# AtmelSMD328NRF.net
KiCad netlist of a schematic drawn in EAGLE
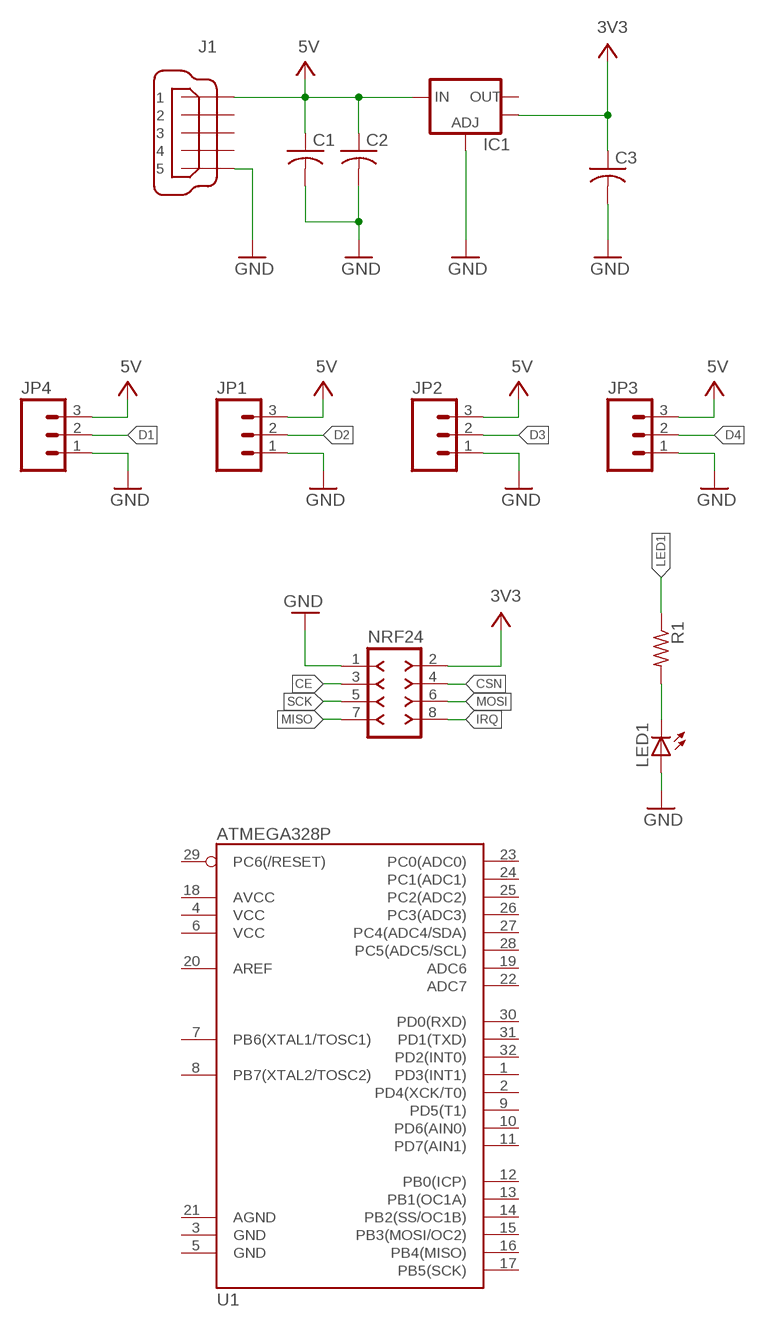
[diagram p0: schematic, sheet 1]

(export (version "E")
  (design (tool "Eeschema 10.0.6"))
  (components
    (comp (ref "C1")
      (value "C-USC0805")
      (footprint "eagle-import:C0805")
      (libsource (lib "eagle-import") (part "C-USC0805"))
    )
    (comp (ref "C2")
      (value "C-USC0805")
      (footprint "eagle-import:C0805")
      (libsource (lib "eagle-import") (part "C-USC0805"))
    )
    (comp (ref "C3")
      (value "C-USC0805")
      (footprint "eagle-import:C0805")
      (libsource (lib "eagle-import") (part "C-USC0805"))
    )
    (comp (ref "IC1")
      (value "V_REG_LM1117SOT223")
      (footprint "eagle-import:SOT223")
      (libsource (lib "eagle-import") (part "V_REG_LM1117SOT223"))
    )
    (comp (ref "J1")
      (value "MICRO-USB-ZX62R-B-5P")
      (footprint "eagle-import:ZX62R-B-5P")
      (libsource (lib "eagle-import") (part "MICRO-USB-ZX62R-B-5P"))
    )
    (comp (ref "JP1")
      (value "M03PTH")
      (footprint "eagle-import:1X03")
      (libsource (lib "eagle-import") (part "M03PTH"))
    )
    (comp (ref "JP2")
      (value "M03PTH")
      (footprint "eagle-import:1X03")
      (libsource (lib "eagle-import") (part "M03PTH"))
    )
    (comp (ref "JP3")
      (value "M03PTH")
      (footprint "eagle-import:1X03")
      (libsource (lib "eagle-import") (part "M03PTH"))
    )
    (comp (ref "JP4")
      (value "M03PTH")
      (footprint "eagle-import:1X03")
      (libsource (lib "eagle-import") (part "M03PTH"))
    )
    (comp (ref "LED1")
      (value "LEDCHIPLED_0805")
      (footprint "eagle-import:CHIPLED_0805")
      (libsource (lib "eagle-import") (part "LEDCHIPLED_0805"))
    )
    (comp (ref "NRF24")
      (value "F-2X04-DIL-100")
      (footprint "eagle-import:DIL-100-2X04")
      (libsource (lib "eagle-import") (part "F-2X04-DIL-100"))
    )
    (comp (ref "R1")
      (value "R-US_R0805")
      (footprint "eagle-import:R0805")
      (libsource (lib "eagle-import") (part "R-US_R0805"))
    )
    (comp (ref "U1")
      (value "ATMEGA328P")
      (footprint "eagle-import:TQFP32-08")
      (libsource (lib "eagle-import") (part "ATMEGA328_SMT"))
    )
  )
  (nets
    (net (code "1") (name "3V3") (class "Default")
      (node (ref "C3") (pin "1") (pinfunction "1_1") (pintype "passive"))
      (node (ref "IC1") (pin "4") (pinfunction "OUT_4") (pintype "output"))
      (node (ref "NRF24") (pin "2") (pinfunction "2_2") (pintype "passive"))
    )
    (net (code "2") (name "5V") (class "Default")
      (node (ref "C1") (pin "1") (pinfunction "1_1") (pintype "passive"))
      (node (ref "C2") (pin "1") (pinfunction "1_1") (pintype "passive"))
      (node (ref "IC1") (pin "3") (pinfunction "IN_3") (pintype "input"))
      (node (ref "J1") (pin "1") (pinfunction "1_1") (pintype "input"))
      (node (ref "JP1") (pin "3") (pinfunction "3_3") (pintype "passive"))
      (node (ref "JP2") (pin "3") (pinfunction "3_3") (pintype "passive"))
      (node (ref "JP3") (pin "3") (pinfunction "3_3") (pintype "passive"))
      (node (ref "JP4") (pin "3") (pinfunction "3_3") (pintype "passive"))
    )
    (net (code "3") (name "CE") (class "Default")
      (node (ref "NRF24") (pin "3") (pinfunction "3_3") (pintype "passive"))
    )
    (net (code "4") (name "CSN") (class "Default")
      (node (ref "NRF24") (pin "4") (pinfunction "4_4") (pintype "passive"))
    )
    (net (code "5") (name "D1") (class "Default")
      (node (ref "JP4") (pin "2") (pinfunction "2_2") (pintype "passive"))
    )
    (net (code "6") (name "D2") (class "Default")
      (node (ref "JP1") (pin "2") (pinfunction "2_2") (pintype "passive"))
    )
    (net (code "7") (name "D3") (class "Default")
      (node (ref "JP2") (pin "2") (pinfunction "2_2") (pintype "passive"))
    )
    (net (code "8") (name "D4") (class "Default")
      (node (ref "JP3") (pin "2") (pinfunction "2_2") (pintype "passive"))
    )
    (net (code "9") (name "GND") (class "Default")
      (node (ref "C1") (pin "2") (pinfunction "2_2") (pintype "passive"))
      (node (ref "C2") (pin "2") (pinfunction "2_2") (pintype "passive"))
      (node (ref "C3") (pin "2") (pinfunction "2_2") (pintype "passive"))
      (node (ref "IC1") (pin "1") (pinfunction "ADJ_1") (pintype "input"))
      (node (ref "J1") (pin "5") (pinfunction "5_5") (pintype "input"))
      (node (ref "JP1") (pin "1") (pinfunction "1_1") (pintype "passive"))
      (node (ref "JP2") (pin "1") (pinfunction "1_1") (pintype "passive"))
      (node (ref "JP3") (pin "1") (pinfunction "1_1") (pintype "passive"))
      (node (ref "JP4") (pin "1") (pinfunction "1_1") (pintype "passive"))
      (node (ref "LED1") (pin "A") (pinfunction "A_A") (pintype "passive"))
      (node (ref "NRF24") (pin "1") (pinfunction "1_1") (pintype "passive"))
    )
    (net (code "10") (name "IRQ") (class "Default")
      (node (ref "NRF24") (pin "8") (pinfunction "8_8") (pintype "passive"))
    )
    (net (code "11") (name "LED1") (class "Default")
      (node (ref "R1") (pin "1") (pinfunction "1_1") (pintype "passive"))
    )
    (net (code "12") (name "MISO") (class "Default")
      (node (ref "NRF24") (pin "7") (pinfunction "7_7") (pintype "passive"))
    )
    (net (code "13") (name "MOSI") (class "Default")
      (node (ref "NRF24") (pin "6") (pinfunction "6_6") (pintype "passive"))
    )
    (net (code "14") (name "Net-(LED1-PadC)") (class "Default")
      (node (ref "LED1") (pin "C") (pinfunction "C_C") (pintype "passive"))
      (node (ref "R1") (pin "2") (pinfunction "2_2") (pintype "passive"))
    )
    (net (code "15") (name "SCK") (class "Default")
      (node (ref "NRF24") (pin "5") (pinfunction "5_5") (pintype "passive"))
    )
    (net (code "16") (name "unconnected-(IC1-OUT-Pad2)") (class "Default")
      (node (ref "IC1") (pin "2") (pinfunction "OUT_2") (pintype "output"))
    )
    (net (code "17") (name "unconnected-(J1-Pad2)") (class "Default")
      (node (ref "J1") (pin "2") (pinfunction "2_2") (pintype "input"))
    )
    (net (code "18") (name "unconnected-(J1-Pad3)") (class "Default")
      (node (ref "J1") (pin "3") (pinfunction "3_3") (pintype "input"))
    )
    (net (code "19") (name "unconnected-(J1-Pad4)") (class "Default")
      (node (ref "J1") (pin "4") (pinfunction "4_4") (pintype "input"))
    )
    (net (code "20") (name "unconnected-(U1-ADC6-Pad19)") (class "Default")
      (node (ref "U1") (pin "19") (pinfunction "ADC6_19") (pintype "bidirectional"))
    )
    (net (code "21") (name "unconnected-(U1-ADC7-Pad22)") (class "Default")
      (node (ref "U1") (pin "22") (pinfunction "ADC7_22") (pintype "bidirectional"))
    )
    (net (code "22") (name "unconnected-(U1-AGND-Pad21)") (class "Default")
      (node (ref "U1") (pin "21") (pinfunction "AGND_21") (pintype "bidirectional"))
    )
    (net (code "23") (name "unconnected-(U1-AREF-Pad20)") (class "Default")
      (node (ref "U1") (pin "20") (pinfunction "AREF_20") (pintype "bidirectional"))
    )
    (net (code "24") (name "unconnected-(U1-AVCC-Pad18)") (class "Default")
      (node (ref "U1") (pin "18") (pinfunction "AVCC_18") (pintype "bidirectional"))
    )
    (net (code "25") (name "unconnected-(U1-GND-Pad3)") (class "Default")
      (node (ref "U1") (pin "3") (pinfunction "GND_3") (pintype "bidirectional"))
    )
    (net (code "26") (name "unconnected-(U1-GND-Pad5)") (class "Default")
      (node (ref "U1") (pin "5") (pinfunction "GND_5") (pintype "bidirectional"))
    )
    (net (code "27") (name "unconnected-(U1-PB0(ICP)-Pad12)") (class "Default")
      (node (ref "U1") (pin "12") (pinfunction "PB0(ICP)_12") (pintype "bidirectional"))
    )
    (net (code "28") (name "unconnected-(U1-PB1(OC1A)-Pad13)") (class "Default")
      (node (ref "U1") (pin "13") (pinfunction "PB1(OC1A)_13") (pintype "bidirectional"))
    )
    (net (code "29") (name "unconnected-(U1-PB2(SS{slash}OC1B)-Pad14)") (class "Default")
      (node (ref "U1") (pin "14") (pinfunction "PB2(SS/OC1B)_14") (pintype "bidirectional"))
    )
    (net (code "30") (name "unconnected-(U1-PB3(MOSI{slash}OC2)-Pad15)") (class "Default")
      (node (ref "U1") (pin "15") (pinfunction "PB3(MOSI/OC2)_15") (pintype "bidirectional"))
    )
    (net (code "31") (name "unconnected-(U1-PB4(MISO)-Pad16)") (class "Default")
      (node (ref "U1") (pin "16") (pinfunction "PB4(MISO)_16") (pintype "bidirectional"))
    )
    (net (code "32") (name "unconnected-(U1-PB5(SCK)-Pad17)") (class "Default")
      (node (ref "U1") (pin "17") (pinfunction "PB5(SCK)_17") (pintype "bidirectional"))
    )
    (net (code "33") (name "unconnected-(U1-PB6(XTAL1{slash}TOSC1)-Pad7)") (class "Default")
      (node (ref "U1") (pin "7") (pinfunction "PB6(XTAL1/TOSC1)_7") (pintype "bidirectional"))
    )
    (net (code "34") (name "unconnected-(U1-PB7(XTAL2{slash}TOSC2)-Pad8)") (class "Default")
      (node (ref "U1") (pin "8") (pinfunction "PB7(XTAL2/TOSC2)_8") (pintype "bidirectional"))
    )
    (net (code "35") (name "unconnected-(U1-PC0(ADC0)-Pad23)") (class "Default")
      (node (ref "U1") (pin "23") (pinfunction "PC0(ADC0)_23") (pintype "bidirectional"))
    )
    (net (code "36") (name "unconnected-(U1-PC1(ADC1)-Pad24)") (class "Default")
      (node (ref "U1") (pin "24") (pinfunction "PC1(ADC1)_24") (pintype "bidirectional"))
    )
    (net (code "37") (name "unconnected-(U1-PC2(ADC2)-Pad25)") (class "Default")
      (node (ref "U1") (pin "25") (pinfunction "PC2(ADC2)_25") (pintype "bidirectional"))
    )
    (net (code "38") (name "unconnected-(U1-PC3(ADC3)-Pad26)") (class "Default")
      (node (ref "U1") (pin "26") (pinfunction "PC3(ADC3)_26") (pintype "bidirectional"))
    )
    (net (code "39") (name "unconnected-(U1-PC4(ADC4{slash}SDA)-Pad27)") (class "Default")
      (node (ref "U1") (pin "27") (pinfunction "PC4(ADC4/SDA)_27") (pintype "bidirectional"))
    )
    (net (code "40") (name "unconnected-(U1-PC5(ADC5{slash}SCL)-Pad28)") (class "Default")
      (node (ref "U1") (pin "28") (pinfunction "PC5(ADC5/SCL)_28") (pintype "bidirectional"))
    )
    (net (code "41") (name "unconnected-(U1-PC6({slash}RESET)-Pad29)") (class "Default")
      (node (ref "U1") (pin "29") (pinfunction "PC6(/RESET)_29") (pintype "bidirectional"))
    )
    (net (code "42") (name "unconnected-(U1-PD0(RXD)-Pad30)") (class "Default")
      (node (ref "U1") (pin "30") (pinfunction "PD0(RXD)_30") (pintype "bidirectional"))
    )
    (net (code "43") (name "unconnected-(U1-PD1(TXD)-Pad31)") (class "Default")
      (node (ref "U1") (pin "31") (pinfunction "PD1(TXD)_31") (pintype "bidirectional"))
    )
    (net (code "44") (name "unconnected-(U1-PD2(INT0)-Pad32)") (class "Default")
      (node (ref "U1") (pin "32") (pinfunction "PD2(INT0)_32") (pintype "bidirectional"))
    )
    (net (code "45") (name "unconnected-(U1-PD3(INT1)-Pad1)") (class "Default")
      (node (ref "U1") (pin "1") (pinfunction "PD3(INT1)_1") (pintype "bidirectional"))
    )
    (net (code "46") (name "unconnected-(U1-PD4(XCK{slash}T0)-Pad2)") (class "Default")
      (node (ref "U1") (pin "2") (pinfunction "PD4(XCK/T0)_2") (pintype "bidirectional"))
    )
    (net (code "47") (name "unconnected-(U1-PD5(T1)-Pad9)") (class "Default")
      (node (ref "U1") (pin "9") (pinfunction "PD5(T1)_9") (pintype "bidirectional"))
    )
    (net (code "48") (name "unconnected-(U1-PD6(AIN0)-Pad10)") (class "Default")
      (node (ref "U1") (pin "10") (pinfunction "PD6(AIN0)_10") (pintype "bidirectional"))
    )
    (net (code "49") (name "unconnected-(U1-PD7(AIN1)-Pad11)") (class "Default")
      (node (ref "U1") (pin "11") (pinfunction "PD7(AIN1)_11") (pintype "bidirectional"))
    )
    (net (code "50") (name "unconnected-(U1-VCC-Pad4)") (class "Default")
      (node (ref "U1") (pin "4") (pinfunction "VCC_4") (pintype "bidirectional"))
    )
    (net (code "51") (name "unconnected-(U1-VCC-Pad6)") (class "Default")
      (node (ref "U1") (pin "6") (pinfunction "VCC_6") (pintype "bidirectional"))
    )
  )
)
